# main.net
KiCad netlist of a schematic drawn in Altium Designer
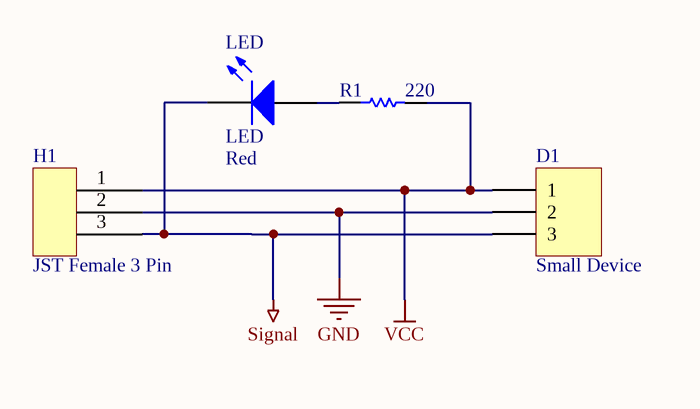
[diagram p0: main.SchDoc]

(export (version "E")
  (design (tool "Eeschema 10.0.6"))
  (components
    (comp (ref "D1")
      (value "Small Device")
      (footprint "HDR1X3")
      (description "Header, 3-Pin")
      (fields (field (name "PUBLISHER") "Altium Limited"))
      (libsource (lib "Miscellaneous Connectors") (part "Header 3"))
    )
    (comp (ref "H1")
      (value "JST Female 3 Pin")
      (footprint "Jst Female 3pin")
      (libsource (lib "Misc Components") (part "JST Female 3 Pin"))
    )
    (comp (ref "LED")
      (value "LED")
      (footprint "Small Blue LED")
      (description "3mm LED")
      (fields (field (name "COLOR") "Red"))
      (libsource (lib "Misc Components") (part "Small LED"))
    )
    (comp (ref "R1")
      (value "220")
      (footprint "AXIAL-0.3")
      (description "Resistor")
      (fields (field (name "Comment") "Res1") (field (name "PUBLISHER") "Altium Limited"))
      (libsource (lib "Miscellaneous Devices") (part "Res1"))
    )
  )
  (nets
    (net (code "1") (name "GND") (class "Default")
      (node (ref "D1") (pin "2") (pinfunction "2_2") (pintype "passive"))
      (node (ref "H1") (pin "2") (pintype "power_in"))
    )
    (net (code "2") (name "Net-(LED-A)") (class "Default")
      (node (ref "LED") (pin "1") (pinfunction "A_1") (pintype "passive"))
      (node (ref "R1") (pin "1") (pinfunction "1_1") (pintype "passive"))
    )
    (net (code "3") (name "Signal") (class "Default")
      (node (ref "D1") (pin "3") (pinfunction "3_3") (pintype "passive"))
      (node (ref "H1") (pin "3") (pintype "power_in"))
      (node (ref "LED") (pin "2") (pinfunction "K_2") (pintype "passive"))
    )
    (net (code "4") (name "VCC") (class "Default")
      (node (ref "D1") (pin "1") (pinfunction "1_1") (pintype "passive"))
      (node (ref "H1") (pin "1") (pintype "power_in"))
      (node (ref "R1") (pin "2") (pinfunction "2_2") (pintype "passive"))
    )
  )
)
